# PS.net
KiCad netlist of a schematic drawn in Altium Designer
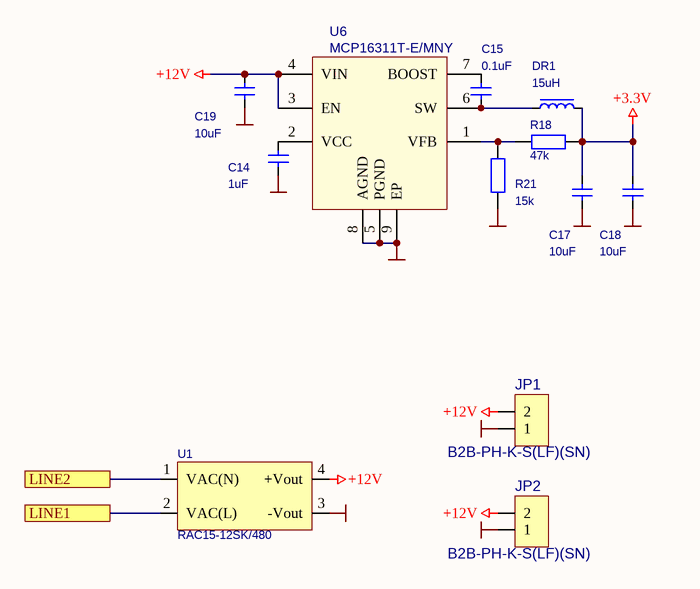
[diagram p0: PS.SchDoc]

(export (version "E")
  (design (tool "Eeschema 10.0.6"))
  (components
    (comp (ref "C14")
      (value "1uF")
      (footprint "C-0805")
      (description "X7R 16V")
      (fields (field (name "MANUFACTURER") "Generic"))
      (libsource (lib "passive") (part "C"))
    )
    (comp (ref "C15")
      (value "0.1uF")
      (footprint "C-0603")
      (description "CAP CER")
      (fields (field (name "MANUFACTURER") "Generic"))
      (libsource (lib "passive") (part "C"))
    )
    (comp (ref "C17")
      (value "10uF")
      (footprint "C-1206")
      (description "X7R 16V")
      (fields (field (name "MANUFACTURER") "Generic"))
      (libsource (lib "passive") (part "C"))
    )
    (comp (ref "C18")
      (value "10uF")
      (footprint "C-1206")
      (description "X7R 16V")
      (fields (field (name "MANUFACTURER") "Generic"))
      (libsource (lib "passive") (part "C"))
    )
    (comp (ref "C19")
      (value "10uF")
      (footprint "C-1206")
      (description "X7R 16V")
      (fields (field (name "MANUFACTURER") "Generic"))
      (libsource (lib "passive") (part "C"))
    )
    (comp (ref "DR1")
      (value "15uH")
      (footprint "NRS4018")
      (description "FIXED IND 15UH 850MA 252MOHM SMD")
      (fields
        (field (name "MANUFACTURER PART NUMBER") "NRS4018T150MDGJ")
        (field (name "MANUFACTURER") "Taiyo Yuden")
      )
      (libsource (lib "passive") (part "L*"))
    )
    (comp (ref "JP1")
      (value "B2B-PH-K-S(LF)(SN)")
      (footprint "JST_B2B-PH-K-S")
      (description "CONN HEADER VERT 2POS 2MM")
      (fields (field (name "MANUFACTURER") "JST Sales America Inc."))
      (libsource (lib "Connectors") (part "CON2"))
    )
    (comp (ref "JP2")
      (value "B2B-PH-K-S(LF)(SN)")
      (footprint "JST_B2B-PH-K-S")
      (description "CONN HEADER VERT 2POS 2MM")
      (fields (field (name "MANUFACTURER") "JST Sales America Inc."))
      (libsource (lib "Connectors") (part "CON2"))
    )
    (comp (ref "R18")
      (value "47k")
      (footprint "R-0603")
      (description "Resistor")
      (fields (field (name "MANUFACTURER") "Generic"))
      (libsource (lib "passive") (part "R"))
    )
    (comp (ref "R21")
      (value "15k")
      (footprint "R-0603")
      (description "Resistor")
      (fields (field (name "MANUFACTURER") "Generic"))
      (libsource (lib "passive") (part "R"))
    )
    (comp (ref "U1")
      (value "RAC15-12SK/480")
      (footprint "RAC15")
      (description "15W AC/DC-CONVERTER")
      (fields (field (name "MANUFACTURER") "Recom Power"))
      (libsource (lib "ic") (part "RAC15"))
    )
    (comp (ref "U6")
      (value "MCP16311T-E/MNY")
      (footprint "TDFN8")
      (description "IC REG BUCK ADJUSTABLE 1A 8TDFN")
      (fields (field (name "MANUFACTURER") "Microchip Technology"))
      (libsource (lib "ic") (part "MCP16311"))
    )
  )
  (nets
    (net (code "1") (name "+3.3V") (class "Default")
      (node (ref "C17") (pin "1") (pinfunction "1_1") (pintype "passive"))
      (node (ref "C18") (pin "1") (pinfunction "1_1") (pintype "passive"))
      (node (ref "DR1") (pin "2") (pinfunction "2_2") (pintype "passive"))
      (node (ref "R18") (pin "2") (pinfunction "2_2") (pintype "passive"))
    )
    (net (code "2") (name "+12V") (class "Default")
      (node (ref "C19") (pin "1") (pinfunction "1_1") (pintype "passive"))
      (node (ref "JP1") (pin "2") (pinfunction "2_2") (pintype "passive"))
      (node (ref "JP2") (pin "2") (pinfunction "2_2") (pintype "passive"))
      (node (ref "U1") (pin "4") (pinfunction "+Vout_4") (pintype "passive"))
      (node (ref "U6") (pin "3") (pinfunction "EN_3") (pintype "passive"))
      (node (ref "U6") (pin "4") (pinfunction "VIN_4") (pintype "passive"))
    )
    (net (code "3") (name "/LINE1") (class "Default")
      (node (ref "U1") (pin "2") (pinfunction "VAC(L)_2") (pintype "passive"))
    )
    (net (code "4") (name "/LINE2") (class "Default")
      (node (ref "U1") (pin "1") (pinfunction "VAC(N)_1") (pintype "passive"))
    )
    (net (code "5") (name "GND") (class "Default")
      (node (ref "C14") (pin "1") (pinfunction "1_1") (pintype "passive"))
      (node (ref "C17") (pin "2") (pinfunction "2_2") (pintype "passive"))
      (node (ref "C18") (pin "2") (pinfunction "2_2") (pintype "passive"))
      (node (ref "C19") (pin "2") (pinfunction "2_2") (pintype "passive"))
      (node (ref "JP1") (pin "1") (pinfunction "1_1") (pintype "passive"))
      (node (ref "JP2") (pin "1") (pinfunction "1_1") (pintype "passive"))
      (node (ref "R21") (pin "2") (pinfunction "2_2") (pintype "passive"))
      (node (ref "U1") (pin "3") (pinfunction "-Vout_3") (pintype "passive"))
      (node (ref "U6") (pin "5") (pinfunction "PGND_5") (pintype "passive"))
      (node (ref "U6") (pin "8") (pinfunction "AGND_8") (pintype "passive"))
      (node (ref "U6") (pin "9") (pinfunction "EP_9") (pintype "passive"))
    )
    (net (code "6") (name "Net-(U6-BOOST)") (class "Default")
      (node (ref "C15") (pin "2") (pinfunction "2_2") (pintype "passive"))
      (node (ref "U6") (pin "7") (pinfunction "BOOST_7") (pintype "passive"))
    )
    (net (code "7") (name "Net-(U6-SW)") (class "Default")
      (node (ref "C15") (pin "1") (pinfunction "1_1") (pintype "passive"))
      (node (ref "DR1") (pin "1") (pinfunction "1_1") (pintype "passive"))
      (node (ref "U6") (pin "6") (pinfunction "SW_6") (pintype "passive"))
    )
    (net (code "8") (name "Net-(U6-VCC)") (class "Default")
      (node (ref "C14") (pin "2") (pinfunction "2_2") (pintype "passive"))
      (node (ref "U6") (pin "2") (pinfunction "VCC_2") (pintype "passive"))
    )
    (net (code "9") (name "Net-(U6-VFB)") (class "Default")
      (node (ref "R18") (pin "1") (pinfunction "1_1") (pintype "passive"))
      (node (ref "R21") (pin "1") (pinfunction "1_1") (pintype "passive"))
      (node (ref "U6") (pin "1") (pinfunction "VFB_1") (pintype "passive"))
    )
  )
)
